# 07-NET.net
KiCad netlist of a schematic drawn in Altium Designer
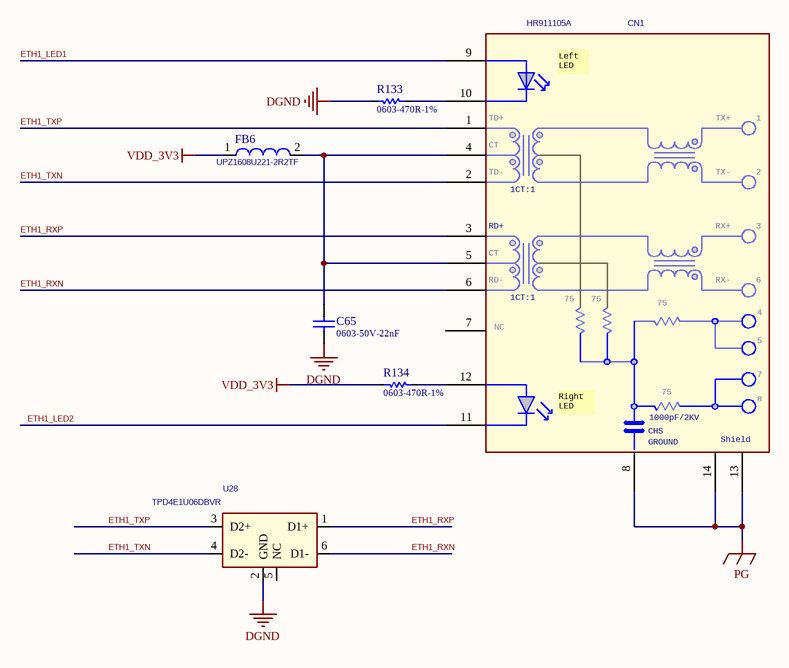
[diagram p0: 07-NET.SchDoc]

(export (version "E")
  (design (tool "Eeschema 10.0.6"))
  (components
    (comp (ref "C65")
      (value "0603-50V-22nF")
      (footprint "0603C")
      (description "Capacitor")
      (fields (field (name "PUBLISHER") "Altium Limited"))
      (libsource (lib "Miscellaneous Devices") (part "Cap"))
    )
    (comp (ref "CN1")
      (value "HR911105A")
      (footprint "HY911105A")
      (fields (field (name "MANUFACTURER") "HanRun"))
      (libsource (lib "*") (part "HR911105A"))
    )
    (comp (ref "FB6")
      (value "UPZ1608U221-2R2TF")
      (footprint "0603L")
      (libsource (lib "MYB-IMX28X-V11_Library") (part "FER_BEAD"))
    )
    (comp (ref "R133")
      (value "0603-470R-1%")
      (footprint "0603R")
      (description "Resistor")
      (fields (field (name "PUBLISHER") "Altium Limited"))
      (libsource (lib "Miscellaneous Devices") (part "Res1"))
    )
    (comp (ref "R134")
      (value "0603-470R-1%")
      (footprint "0603R")
      (description "Resistor")
      (fields (field (name "PUBLISHER") "Altium Limited"))
      (libsource (lib "Miscellaneous Devices") (part "Res1"))
    )
    (comp (ref "U28")
      (value "TPD4E1U06DBVR")
      (footprint "LC-SOT-23-6")
      (description "IC,ESD Suppressor Diode Arrays ±15KV 6-Pin SOT-23")
      (fields (field (name "MANUFACTURER") "TI"))
      (libsource (lib "*") (part "TPD4E1U06DBVR"))
    )
  )
  (nets
    (net (code "1") (name "/ETH1_LED1") (class "Default")
      (node (ref "CN1") (pin "9") (pinfunction "LLED+_9") (pintype "passive"))
    )
    (net (code "2") (name "/ETH1_LED2") (class "Default")
      (node (ref "CN1") (pin "11") (pinfunction "RLED-_11") (pintype "passive"))
    )
    (net (code "3") (name "/ETH1_RXN") (class "Default")
      (node (ref "CN1") (pin "6") (pinfunction "P6_6") (pintype "passive"))
      (node (ref "U28") (pin "6") (pinfunction "D1-_6") (pintype "passive"))
    )
    (net (code "4") (name "/ETH1_RXP") (class "Default")
      (node (ref "CN1") (pin "3") (pinfunction "P3_3") (pintype "passive"))
      (node (ref "U28") (pin "1") (pinfunction "D1+_1") (pintype "passive"))
    )
    (net (code "5") (name "/ETH1_TXN") (class "Default")
      (node (ref "CN1") (pin "2") (pinfunction "P2_2") (pintype "passive"))
      (node (ref "U28") (pin "4") (pinfunction "D2-_4") (pintype "passive"))
    )
    (net (code "6") (name "/ETH1_TXP") (class "Default")
      (node (ref "CN1") (pin "1") (pinfunction "P1_1") (pintype "passive"))
      (node (ref "U28") (pin "3") (pinfunction "D2+_3") (pintype "passive"))
    )
    (net (code "7") (name "DGND") (class "Default")
      (node (ref "C65") (pin "2") (pinfunction "2_2") (pintype "passive"))
      (node (ref "R133") (pin "1") (pinfunction "1_1") (pintype "passive"))
      (node (ref "U28") (pin "2") (pinfunction "GND_2") (pintype "passive"))
    )
    (net (code "8") (name "Net-(CN1-LLED-)") (class "Default")
      (node (ref "CN1") (pin "10") (pinfunction "LLED-_10") (pintype "passive"))
      (node (ref "R133") (pin "2") (pinfunction "2_2") (pintype "passive"))
    )
    (net (code "9") (name "Net-(CN1-P4)") (class "Default")
      (node (ref "C65") (pin "1") (pinfunction "1_1") (pintype "passive"))
      (node (ref "CN1") (pin "4") (pinfunction "P4_4") (pintype "passive"))
      (node (ref "CN1") (pin "5") (pinfunction "P5_5") (pintype "passive"))
      (node (ref "FB6") (pin "2") (pinfunction "2_2") (pintype "passive"))
    )
    (net (code "10") (name "Net-(CN1-RLED+)") (class "Default")
      (node (ref "CN1") (pin "12") (pinfunction "RLED+_12") (pintype "passive"))
      (node (ref "R134") (pin "2") (pinfunction "2_2") (pintype "passive"))
    )
    (net (code "11") (name "PG") (class "Default")
      (node (ref "CN1") (pin "13") (pinfunction "S1_13") (pintype "passive"))
      (node (ref "CN1") (pin "14") (pinfunction "S2_14") (pintype "passive"))
      (node (ref "CN1") (pin "8") (pinfunction "P8_8") (pintype "passive"))
    )
    (net (code "12") (name "VDD_3V3") (class "Default")
      (node (ref "FB6") (pin "1") (pinfunction "1_1") (pintype "passive"))
      (node (ref "R134") (pin "1") (pinfunction "1_1") (pintype "passive"))
    )
    (net (code "13") (name "unconnected-(CN1-P7-Pad7)") (class "Default")
      (node (ref "CN1") (pin "7") (pinfunction "P7_7") (pintype "passive"))
    )
    (net (code "14") (name "unconnected-(U28-NC-Pad5)") (class "Default")
      (node (ref "U28") (pin "5") (pinfunction "NC_5") (pintype "passive"))
    )
  )
)
